# atmega8.net
KiCad netlist of a schematic drawn in EAGLE
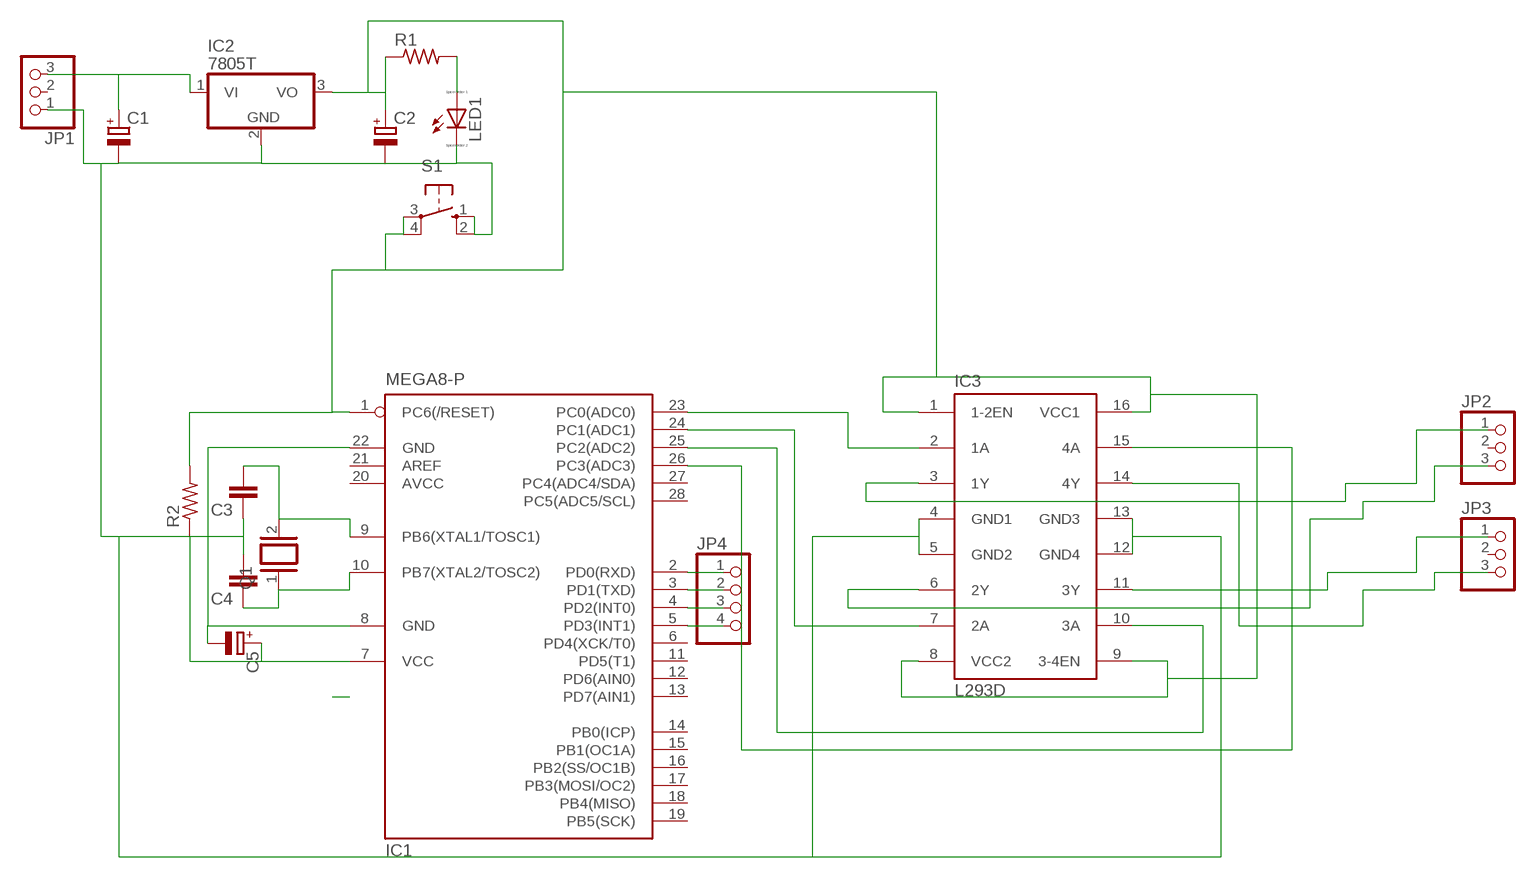
[diagram p0: schematic, sheet 1]

(export (version "E")
  (design (tool "Eeschema 10.0.6"))
  (components
    (comp (ref "C1")
      (value "CPOL-EUE5-6")
      (footprint "eagle-import:E5-6")
      (libsource (lib "eagle-import") (part "CPOL-EUE5-6"))
    )
    (comp (ref "C2")
      (value "CPOL-EUE5-6")
      (footprint "eagle-import:E5-6")
      (libsource (lib "eagle-import") (part "CPOL-EUE5-6"))
    )
    (comp (ref "C3")
      (value "C-EU025-025X050")
      (footprint "eagle-import:C025-025X050")
      (libsource (lib "eagle-import") (part "C-EU025-025X050"))
    )
    (comp (ref "C4")
      (value "C-EU025-025X050")
      (footprint "eagle-import:C025-025X050")
      (libsource (lib "eagle-import") (part "C-EU025-025X050"))
    )
    (comp (ref "C5")
      (value "CPOL-EUE5-6")
      (footprint "eagle-import:E5-6")
      (libsource (lib "eagle-import") (part "CPOL-EUE5-6"))
    )
    (comp (ref "IC1")
      (value "MEGA8-P")
      (footprint "eagle-import:DIL28-3")
      (libsource (lib "eagle-import") (part "MEGA8-P"))
    )
    (comp (ref "IC2")
      (value "7805T")
      (footprint "eagle-import:TO220H")
      (libsource (lib "eagle-import") (part "78T05"))
    )
    (comp (ref "IC3")
      (value "L293D")
      (footprint "eagle-import:DIL16")
      (libsource (lib "eagle-import") (part "L293D"))
    )
    (comp (ref "JP1")
      (value "PINHD-1X3")
      (footprint "eagle-import:1X03")
      (libsource (lib "eagle-import") (part "PINHD-1X3"))
    )
    (comp (ref "JP2")
      (value "PINHD-1X3")
      (footprint "eagle-import:1X03")
      (libsource (lib "eagle-import") (part "PINHD-1X3"))
    )
    (comp (ref "JP3")
      (value "PINHD-1X3")
      (footprint "eagle-import:1X03")
      (libsource (lib "eagle-import") (part "PINHD-1X3"))
    )
    (comp (ref "JP4")
      (value "PINHD-1X4")
      (footprint "eagle-import:1X04")
      (libsource (lib "eagle-import") (part "PINHD-1X4"))
    )
    (comp (ref "LED1")
      (value "LED_ELD260")
      (footprint "eagle-import:LED_LD260")
      (libsource (lib "eagle-import") (part "LED_ELD260"))
    )
    (comp (ref "Q1")
      (value "XTAL/S")
      (footprint "eagle-import:QS")
      (libsource (lib "eagle-import") (part "XTAL/S"))
    )
    (comp (ref "R1")
      (value "R-US_0204/7")
      (footprint "eagle-import:0204_7")
      (libsource (lib "eagle-import") (part "R-US_0204/7"))
    )
    (comp (ref "R2")
      (value "R-US_0204/7")
      (footprint "eagle-import:0204_7")
      (libsource (lib "eagle-import") (part "R-US_0204/7"))
    )
    (comp (ref "S1")
      (value "10-XX")
      (footprint "eagle-import:B3F-10XX")
      (fields (field (name "MPN") "B3F-1000"))
      (libsource (lib "eagle-import") (part "10-XX"))
    )
  )
  (nets
    (net (code "1") (name "/AVCC") (class "Default")
      (node (ref "IC1") (pin "20") (pinfunction "AVCC_20") (pintype "power_in"))
    )
    (net (code "2") (name "Net-(IC1-PB6(XTAL1{slash}TOSC1))") (class "Default")
      (node (ref "C3") (pin "2") (pinfunction "2_2") (pintype "passive"))
      (node (ref "IC1") (pin "9") (pinfunction "PB6(XTAL1/TOSC1)_9") (pintype "bidirectional"))
      (node (ref "Q1") (pin "2") (pinfunction "2_2") (pintype "passive"))
    )
    (net (code "3") (name "Net-(IC1-PB7(XTAL2{slash}TOSC2))") (class "Default")
      (node (ref "C4") (pin "1") (pinfunction "1_1") (pintype "passive"))
      (node (ref "IC1") (pin "10") (pinfunction "PB7(XTAL2/TOSC2)_10") (pintype "bidirectional"))
      (node (ref "Q1") (pin "1") (pinfunction "1_1") (pintype "passive"))
    )
    (net (code "4") (name "Net-(IC1-PC0(ADC0))") (class "Default")
      (node (ref "IC1") (pin "23") (pinfunction "PC0(ADC0)_23") (pintype "bidirectional"))
      (node (ref "IC3") (pin "2") (pinfunction "1A_2") (pintype "input"))
    )
    (net (code "5") (name "Net-(IC1-PC1(ADC1))") (class "Default")
      (node (ref "IC1") (pin "24") (pinfunction "PC1(ADC1)_24") (pintype "bidirectional"))
      (node (ref "IC3") (pin "7") (pinfunction "2A_7") (pintype "input"))
    )
    (net (code "6") (name "Net-(IC1-PC2(ADC2))") (class "Default")
      (node (ref "IC1") (pin "25") (pinfunction "PC2(ADC2)_25") (pintype "bidirectional"))
      (node (ref "IC3") (pin "10") (pinfunction "3A_10") (pintype "input"))
    )
    (net (code "7") (name "Net-(IC1-PC3(ADC3))") (class "Default")
      (node (ref "IC1") (pin "26") (pinfunction "PC3(ADC3)_26") (pintype "bidirectional"))
      (node (ref "IC3") (pin "15") (pinfunction "4A_15") (pintype "input"))
    )
    (net (code "8") (name "Net-(IC1-PC6({slash}RESET))") (class "Default")
      (node (ref "C2") (pin "+") (pinfunction "+_+") (pintype "passive"))
      (node (ref "IC1") (pin "1") (pinfunction "PC6(/RESET)_1") (pintype "bidirectional"))
      (node (ref "IC2") (pin "3") (pinfunction "VO_3") (pintype "passive"))
      (node (ref "IC3") (pin "1") (pinfunction "1-2EN_1") (pintype "input"))
      (node (ref "IC3") (pin "16") (pinfunction "VCC1_16") (pintype "power_in"))
      (node (ref "IC3") (pin "8") (pinfunction "VCC2_8") (pintype "power_in"))
      (node (ref "IC3") (pin "9") (pinfunction "3-4EN_9") (pintype "input"))
      (node (ref "R1") (pin "1") (pinfunction "1_1") (pintype "passive"))
      (node (ref "R2") (pin "2") (pinfunction "2_2") (pintype "passive"))
      (node (ref "S1") (pin "3") (pinfunction "P_3") (pintype "passive"))
      (node (ref "S1") (pin "4") (pinfunction "P1_4") (pintype "passive"))
    )
    (net (code "9") (name "Net-(IC1-PD0(RXD))") (class "Default")
      (node (ref "IC1") (pin "2") (pinfunction "PD0(RXD)_2") (pintype "bidirectional"))
      (node (ref "JP4") (pin "1") (pinfunction "1_1") (pintype "passive"))
    )
    (net (code "10") (name "Net-(IC1-PD1(TXD))") (class "Default")
      (node (ref "IC1") (pin "3") (pinfunction "PD1(TXD)_3") (pintype "bidirectional"))
      (node (ref "JP4") (pin "2") (pinfunction "2_2") (pintype "passive"))
    )
    (net (code "11") (name "Net-(IC1-PD2(INT0))") (class "Default")
      (node (ref "IC1") (pin "4") (pinfunction "PD2(INT0)_4") (pintype "bidirectional"))
      (node (ref "JP4") (pin "3") (pinfunction "3_3") (pintype "passive"))
    )
    (net (code "12") (name "Net-(IC1-PD3(INT1))") (class "Default")
      (node (ref "IC1") (pin "5") (pinfunction "PD3(INT1)_5") (pintype "bidirectional"))
      (node (ref "JP4") (pin "4") (pinfunction "4_4") (pintype "passive"))
    )
    (net (code "13") (name "Net-(IC1-VCC)") (class "Default")
      (node (ref "C5") (pin "+") (pinfunction "+_+") (pintype "passive"))
      (node (ref "IC1") (pin "7") (pinfunction "VCC_7") (pintype "power_in"))
      (node (ref "R2") (pin "1") (pinfunction "1_1") (pintype "passive"))
    )
    (net (code "14") (name "Net-(IC2-GND)") (class "Default")
      (node (ref "C1") (pin "-") (pinfunction "-_-") (pintype "passive"))
      (node (ref "C2") (pin "-") (pinfunction "-_-") (pintype "passive"))
      (node (ref "C3") (pin "1") (pinfunction "1_1") (pintype "passive"))
      (node (ref "C4") (pin "2") (pinfunction "2_2") (pintype "passive"))
      (node (ref "C5") (pin "-") (pinfunction "-_-") (pintype "passive"))
      (node (ref "IC1") (pin "22") (pinfunction "GND_22") (pintype "power_in"))
      (node (ref "IC1") (pin "8") (pinfunction "GND_8") (pintype "power_in"))
      (node (ref "IC2") (pin "2") (pinfunction "GND_2") (pintype "passive"))
      (node (ref "IC3") (pin "12") (pinfunction "GND4_12") (pintype "power_in"))
      (node (ref "IC3") (pin "13") (pinfunction "GND3_13") (pintype "power_in"))
      (node (ref "IC3") (pin "4") (pinfunction "GND1_4") (pintype "power_in"))
      (node (ref "IC3") (pin "5") (pinfunction "GND2_5") (pintype "power_in"))
      (node (ref "JP1") (pin "1") (pinfunction "1_1") (pintype "passive"))
      (node (ref "LED1") (pin "K") (pinfunction "C_K") (pintype "passive"))
      (node (ref "S1") (pin "1") (pinfunction "S_1") (pintype "passive"))
      (node (ref "S1") (pin "2") (pinfunction "S1_2") (pintype "passive"))
    )
    (net (code "15") (name "Net-(IC2-VI)") (class "Default")
      (node (ref "C1") (pin "+") (pinfunction "+_+") (pintype "passive"))
      (node (ref "IC2") (pin "1") (pinfunction "VI_1") (pintype "input"))
      (node (ref "JP1") (pin "3") (pinfunction "3_3") (pintype "passive"))
    )
    (net (code "16") (name "Net-(IC3-1Y)") (class "Default")
      (node (ref "IC3") (pin "3") (pinfunction "1Y_3") (pintype "output"))
      (node (ref "JP2") (pin "1") (pinfunction "1_1") (pintype "passive"))
    )
    (net (code "17") (name "Net-(IC3-2Y)") (class "Default")
      (node (ref "IC3") (pin "6") (pinfunction "2Y_6") (pintype "output"))
      (node (ref "JP2") (pin "3") (pinfunction "3_3") (pintype "passive"))
    )
    (net (code "18") (name "Net-(IC3-3Y)") (class "Default")
      (node (ref "IC3") (pin "11") (pinfunction "3Y_11") (pintype "output"))
      (node (ref "JP3") (pin "1") (pinfunction "1_1") (pintype "passive"))
    )
    (net (code "19") (name "Net-(IC3-4Y)") (class "Default")
      (node (ref "IC3") (pin "14") (pinfunction "4Y_14") (pintype "output"))
      (node (ref "JP3") (pin "3") (pinfunction "3_3") (pintype "passive"))
    )
    (net (code "20") (name "Net-(LED1-PadA)") (class "Default")
      (node (ref "LED1") (pin "A") (pinfunction "A_A") (pintype "passive"))
      (node (ref "R1") (pin "2") (pinfunction "2_2") (pintype "passive"))
    )
    (net (code "21") (name "unconnected-(IC1-AREF-Pad21)") (class "Default")
      (node (ref "IC1") (pin "21") (pinfunction "AREF_21") (pintype "passive"))
    )
    (net (code "22") (name "unconnected-(IC1-PB0(ICP)-Pad14)") (class "Default")
      (node (ref "IC1") (pin "14") (pinfunction "PB0(ICP)_14") (pintype "bidirectional"))
    )
    (net (code "23") (name "unconnected-(IC1-PB1(OC1A)-Pad15)") (class "Default")
      (node (ref "IC1") (pin "15") (pinfunction "PB1(OC1A)_15") (pintype "bidirectional"))
    )
    (net (code "24") (name "unconnected-(IC1-PB2(SS{slash}OC1B)-Pad16)") (class "Default")
      (node (ref "IC1") (pin "16") (pinfunction "PB2(SS/OC1B)_16") (pintype "bidirectional"))
    )
    (net (code "25") (name "unconnected-(IC1-PB3(MOSI{slash}OC2)-Pad17)") (class "Default")
      (node (ref "IC1") (pin "17") (pinfunction "PB3(MOSI/OC2)_17") (pintype "bidirectional"))
    )
    (net (code "26") (name "unconnected-(IC1-PB4(MISO)-Pad18)") (class "Default")
      (node (ref "IC1") (pin "18") (pinfunction "PB4(MISO)_18") (pintype "bidirectional"))
    )
    (net (code "27") (name "unconnected-(IC1-PB5(SCK)-Pad19)") (class "Default")
      (node (ref "IC1") (pin "19") (pinfunction "PB5(SCK)_19") (pintype "bidirectional"))
    )
    (net (code "28") (name "unconnected-(IC1-PC4(ADC4{slash}SDA)-Pad27)") (class "Default")
      (node (ref "IC1") (pin "27") (pinfunction "PC4(ADC4/SDA)_27") (pintype "bidirectional"))
    )
    (net (code "29") (name "unconnected-(IC1-PC5(ADC5{slash}SCL)-Pad28)") (class "Default")
      (node (ref "IC1") (pin "28") (pinfunction "PC5(ADC5/SCL)_28") (pintype "bidirectional"))
    )
    (net (code "30") (name "unconnected-(IC1-PD4(XCK{slash}T0)-Pad6)") (class "Default")
      (node (ref "IC1") (pin "6") (pinfunction "PD4(XCK/T0)_6") (pintype "bidirectional"))
    )
    (net (code "31") (name "unconnected-(IC1-PD5(T1)-Pad11)") (class "Default")
      (node (ref "IC1") (pin "11") (pinfunction "PD5(T1)_11") (pintype "bidirectional"))
    )
    (net (code "32") (name "unconnected-(IC1-PD6(AIN0)-Pad12)") (class "Default")
      (node (ref "IC1") (pin "12") (pinfunction "PD6(AIN0)_12") (pintype "bidirectional"))
    )
    (net (code "33") (name "unconnected-(IC1-PD7(AIN1)-Pad13)") (class "Default")
      (node (ref "IC1") (pin "13") (pinfunction "PD7(AIN1)_13") (pintype "bidirectional"))
    )
    (net (code "34") (name "unconnected-(JP1-Pad2)") (class "Default")
      (node (ref "JP1") (pin "2") (pinfunction "2_2") (pintype "passive"))
    )
    (net (code "35") (name "unconnected-(JP2-Pad2)") (class "Default")
      (node (ref "JP2") (pin "2") (pinfunction "2_2") (pintype "passive"))
    )
    (net (code "36") (name "unconnected-(JP3-Pad2)") (class "Default")
      (node (ref "JP3") (pin "2") (pinfunction "2_2") (pintype "passive"))
    )
  )
)
